# schematic-version2.net
KiCad netlist of a schematic drawn in EAGLE
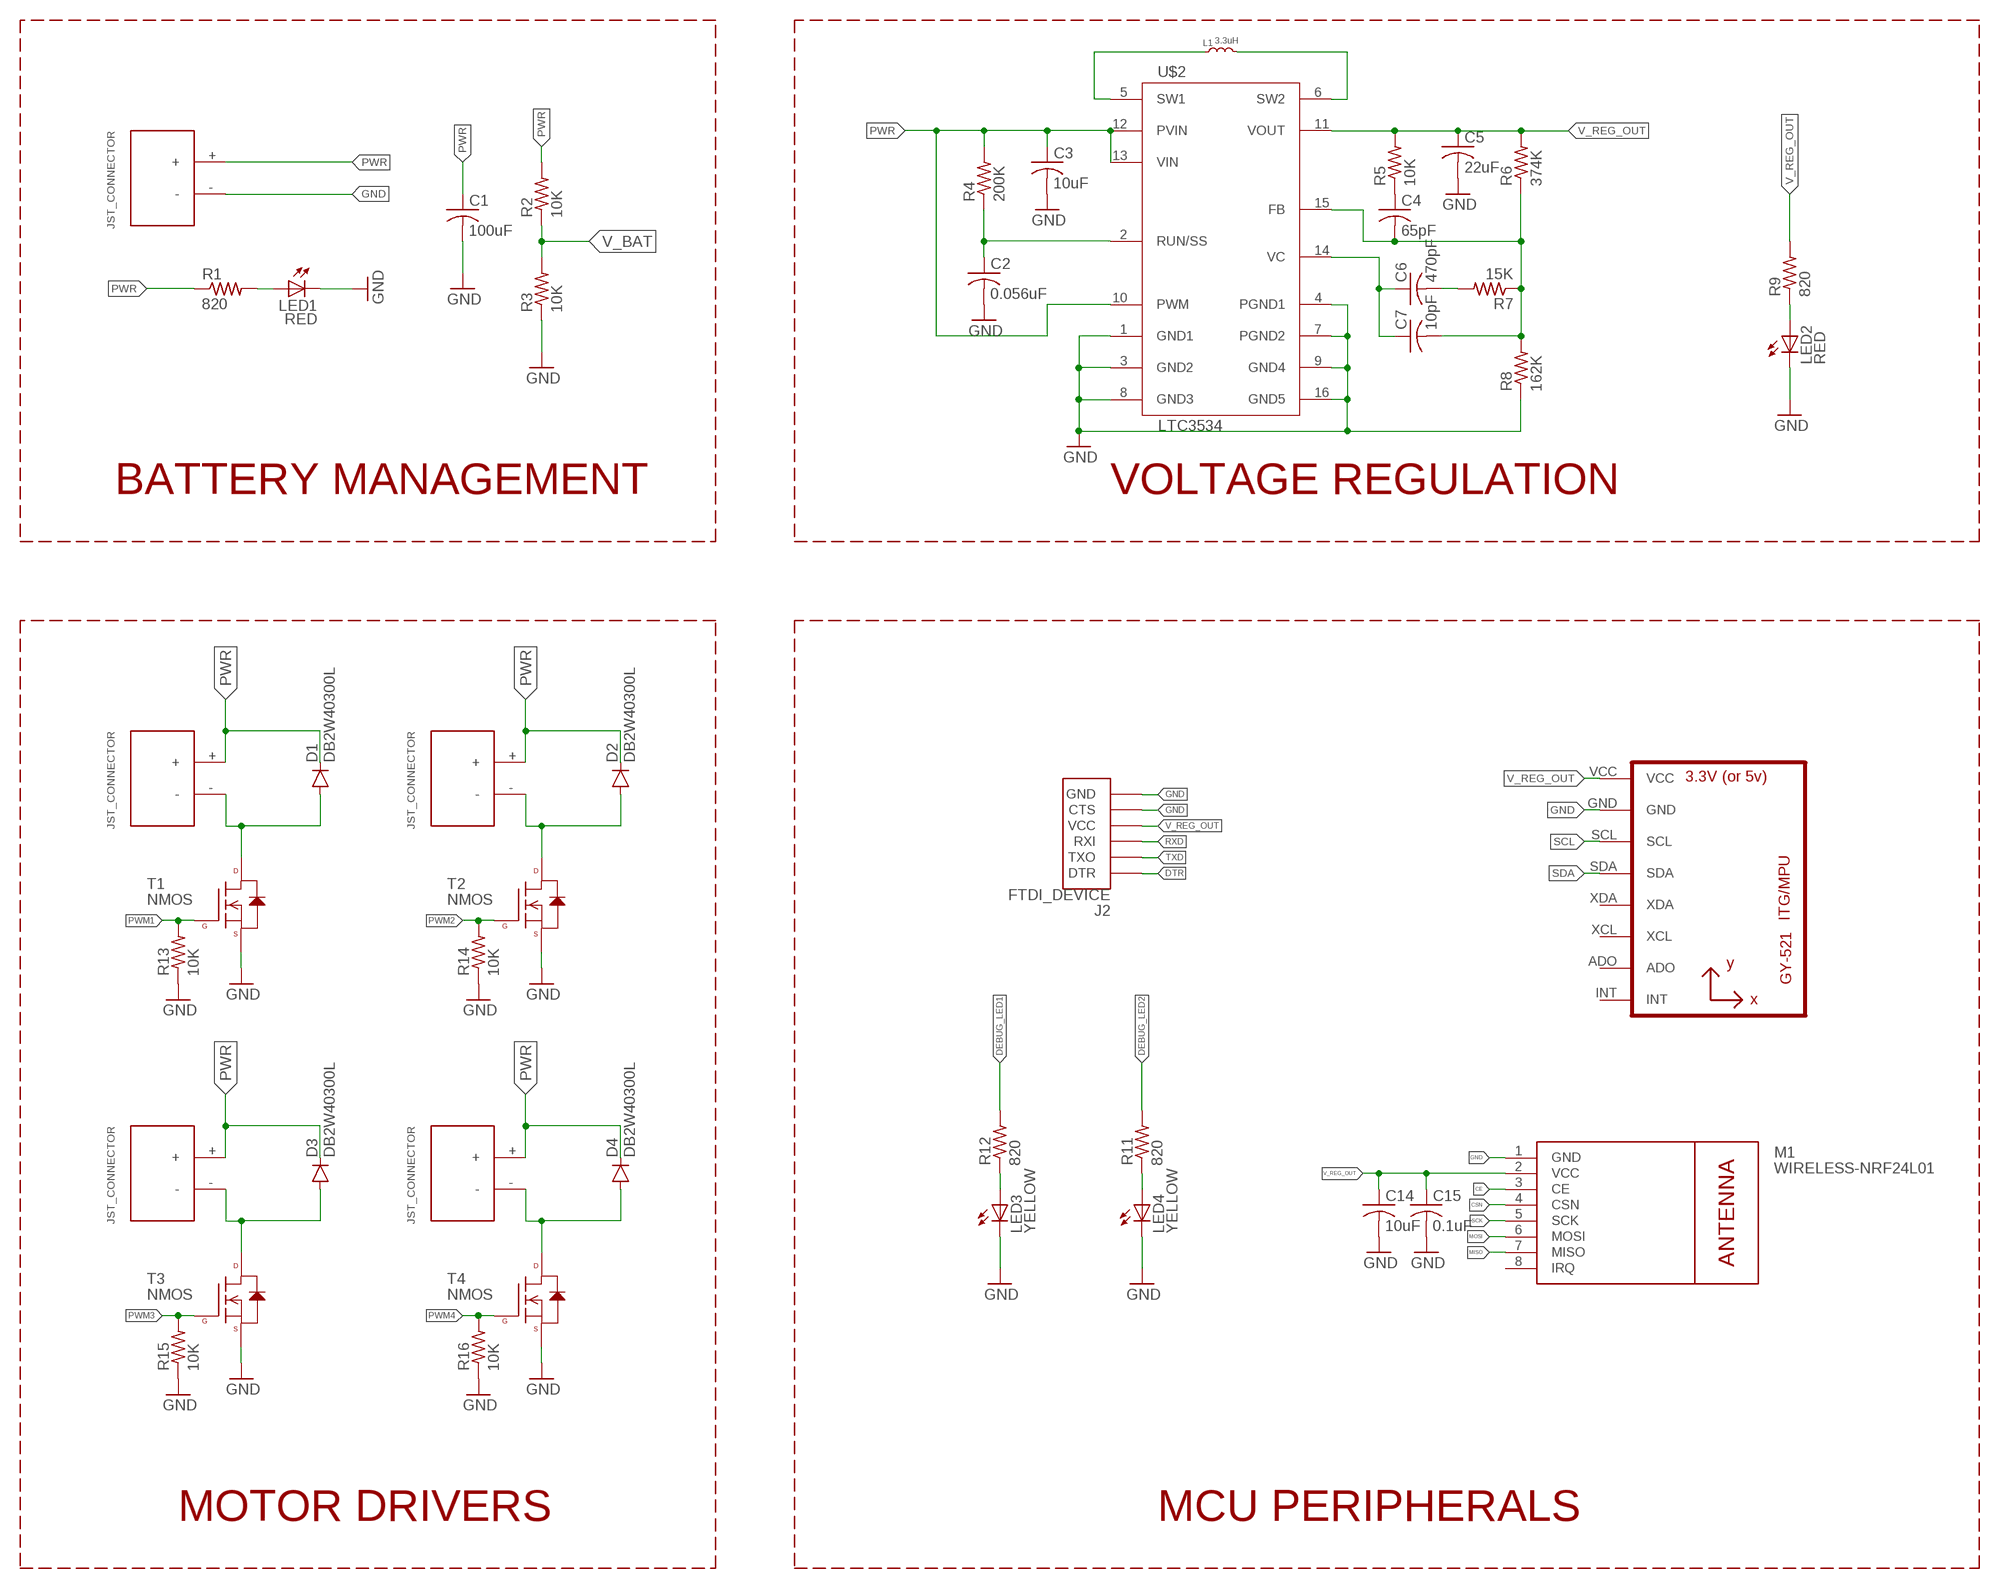
[diagram p0: schematic, sheet 1, part 1 of 2]
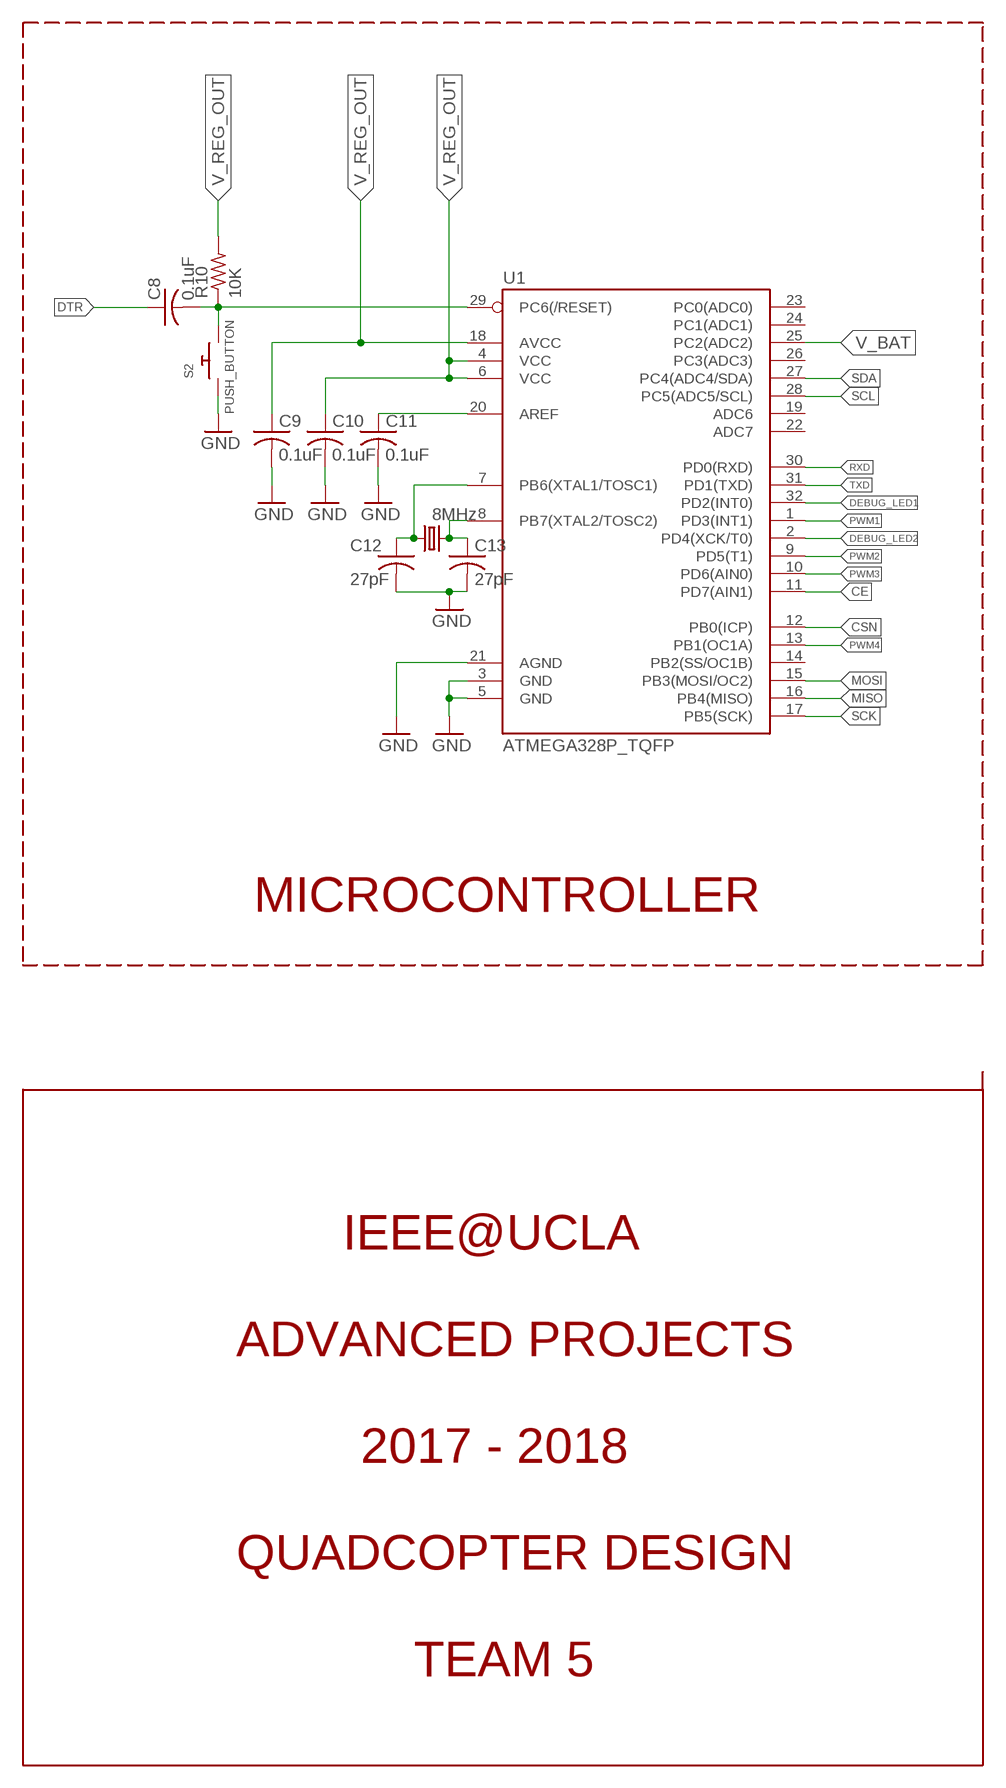
[diagram p1: schematic, sheet 1, part 2 of 2]

(export (version "E")
  (design (tool "Eeschema 10.0.6"))
  (components
    (comp (ref "C1")
      (value "100uF")
      (footprint "eagle-import:C1210")
      (libsource (lib "eagle-import") (part "C-USC1210"))
    )
    (comp (ref "C2")
      (value "0.056uF")
      (footprint "eagle-import:C0603")
      (libsource (lib "eagle-import") (part "resistor_348_C-USC0603"))
    )
    (comp (ref "C3")
      (value "10uF")
      (footprint "eagle-import:C0603")
      (libsource (lib "eagle-import") (part "resistor_348_C-USC0603"))
    )
    (comp (ref "C4")
      (value "65pF")
      (footprint "eagle-import:C1206")
      (libsource (lib "eagle-import") (part "C-USC1206"))
    )
    (comp (ref "C5")
      (value "22uF")
      (footprint "eagle-import:C0603")
      (libsource (lib "eagle-import") (part "resistor_348_C-USC0603"))
    )
    (comp (ref "C6")
      (value "470pF")
      (footprint "eagle-import:C0603")
      (libsource (lib "eagle-import") (part "resistor_348_C-USC0603"))
    )
    (comp (ref "C7")
      (value "10pF")
      (footprint "eagle-import:C0603")
      (libsource (lib "eagle-import") (part "resistor_348_C-USC0603"))
    )
    (comp (ref "C8")
      (value "0.1uF")
      (footprint "eagle-import:C0603")
      (libsource (lib "eagle-import") (part "C-USC0603"))
    )
    (comp (ref "C9")
      (value "0.1uF")
      (footprint "eagle-import:C0603")
      (libsource (lib "eagle-import") (part "C-USC0603"))
    )
    (comp (ref "C10")
      (value "0.1uF")
      (footprint "eagle-import:C0603")
      (libsource (lib "eagle-import") (part "C-USC0603"))
    )
    (comp (ref "C11")
      (value "0.1uF")
      (footprint "eagle-import:C0603")
      (libsource (lib "eagle-import") (part "C-USC0603"))
    )
    (comp (ref "C12")
      (value "27pF")
      (footprint "eagle-import:C0603")
      (libsource (lib "eagle-import") (part "resistor_348_C-USC0603"))
    )
    (comp (ref "C13")
      (value "27pF")
      (footprint "eagle-import:C0603")
      (libsource (lib "eagle-import") (part "resistor_348_C-USC0603"))
    )
    (comp (ref "C14")
      (value "10uF")
      (footprint "eagle-import:C0603")
      (libsource (lib "eagle-import") (part "resistor_348_C-USC0603"))
    )
    (comp (ref "C15")
      (value "0.1uF")
      (footprint "eagle-import:C0603")
      (libsource (lib "eagle-import") (part "resistor_348_C-USC0603"))
    )
    (comp (ref "D1")
      (value "DB2W40300L")
      (footprint "eagle-import:MINI2-F3-B")
      (libsource (lib "eagle-import") (part "DB2W40300L"))
    )
    (comp (ref "D2")
      (value "DB2W40300L")
      (footprint "eagle-import:MINI2-F3-B")
      (libsource (lib "eagle-import") (part "DB2W40300L"))
    )
    (comp (ref "D3")
      (value "DB2W40300L")
      (footprint "eagle-import:MINI2-F3-B")
      (libsource (lib "eagle-import") (part "DB2W40300L"))
    )
    (comp (ref "D4")
      (value "DB2W40300L")
      (footprint "eagle-import:MINI2-F3-B")
      (libsource (lib "eagle-import") (part "DB2W40300L"))
    )
    (comp (ref "J2")
      (value "FTDI_DEVICE")
      (footprint "eagle-import:FTDI_DEVICE_SIDE")
      (libsource (lib "eagle-import") (part "FTDI_DEVICE"))
    )
    (comp (ref "L1")
      (value "3.3uH")
      (footprint "eagle-import:XAL4020")
      (libsource (lib "eagle-import") (part "INDUCTOR.XAL4020"))
    )
    (comp (ref "LED1")
      (value "RED")
      (footprint "eagle-import:SML0603")
      (libsource (lib "eagle-import") (part "LEDSML0603"))
    )
    (comp (ref "LED2")
      (value "RED")
      (footprint "eagle-import:SML0603")
      (libsource (lib "eagle-import") (part "LEDSML0603"))
    )
    (comp (ref "LED3")
      (value "YELLOW")
      (footprint "eagle-import:SML0603")
      (libsource (lib "eagle-import") (part "LEDSML0603"))
    )
    (comp (ref "LED4")
      (value "YELLOW")
      (footprint "eagle-import:SML0603")
      (libsource (lib "eagle-import") (part "LEDSML0603"))
    )
    (comp (ref "M1")
      (value "WIRELESS-NRF24L01")
      (footprint "eagle-import:WIRELESS-NRF24L01")
      (libsource (lib "eagle-import") (part "WIRELESS-NRF24L01"))
    )
    (comp (ref "Q1")
      (value "8MHz")
      (footprint "eagle-import:CSM-7X-DU")
      (libsource (lib "eagle-import") (part "CSM-7X-DU"))
    )
    (comp (ref "R1")
      (value "820")
      (footprint "eagle-import:R0603")
      (libsource (lib "eagle-import") (part "R-US_R0603"))
    )
    (comp (ref "R2")
      (value "10K")
      (footprint "eagle-import:R0603")
      (libsource (lib "eagle-import") (part "resistor_348_R-US_R0603"))
    )
    (comp (ref "R3")
      (value "10K")
      (footprint "eagle-import:R0603")
      (libsource (lib "eagle-import") (part "resistor_348_R-US_R0603"))
    )
    (comp (ref "R4")
      (value "200K")
      (footprint "eagle-import:R0603")
      (libsource (lib "eagle-import") (part "resistor_348_R-US_R0603"))
    )
    (comp (ref "R5")
      (value "10K")
      (footprint "eagle-import:R0603")
      (libsource (lib "eagle-import") (part "resistor_348_R-US_R0603"))
    )
    (comp (ref "R6")
      (value "374K")
      (footprint "eagle-import:R0603")
      (libsource (lib "eagle-import") (part "resistor_348_R-US_R0603"))
    )
    (comp (ref "R7")
      (value "15K")
      (footprint "eagle-import:R0603")
      (libsource (lib "eagle-import") (part "resistor_348_R-US_R0603"))
    )
    (comp (ref "R8")
      (value "162K")
      (footprint "eagle-import:R0603")
      (libsource (lib "eagle-import") (part "resistor_348_R-US_R0603"))
    )
    (comp (ref "R9")
      (value "820")
      (footprint "eagle-import:R0603")
      (libsource (lib "eagle-import") (part "R-US_R0603"))
    )
    (comp (ref "R10")
      (value "10K")
      (footprint "eagle-import:R0603")
      (libsource (lib "eagle-import") (part "resistor_348_R-US_R0603"))
    )
    (comp (ref "R11")
      (value "820")
      (footprint "eagle-import:R0603")
      (libsource (lib "eagle-import") (part "R-US_R0603"))
    )
    (comp (ref "R12")
      (value "820")
      (footprint "eagle-import:R0603")
      (libsource (lib "eagle-import") (part "R-US_R0603"))
    )
    (comp (ref "R13")
      (value "10K")
      (footprint "eagle-import:R0603")
      (libsource (lib "eagle-import") (part "resistor_348_R-US_R0603"))
    )
    (comp (ref "R14")
      (value "10K")
      (footprint "eagle-import:R0603")
      (libsource (lib "eagle-import") (part "resistor_348_R-US_R0603"))
    )
    (comp (ref "R15")
      (value "10K")
      (footprint "eagle-import:R0603")
      (libsource (lib "eagle-import") (part "resistor_348_R-US_R0603"))
    )
    (comp (ref "R16")
      (value "10K")
      (footprint "eagle-import:R0603")
      (libsource (lib "eagle-import") (part "resistor_348_R-US_R0603"))
    )
    (comp (ref "S2")
      (value "PUSH_BUTTON")
      (footprint "eagle-import:PUSHBUTTON_SMD_SJ")
      (libsource (lib "eagle-import") (part "SWITCH_PUSHBUTTONSOFTTOUCHSMD_SJ"))
    )
    (comp (ref "T1")
      (value "NMOS")
      (footprint "eagle-import:SOT23-3")
      (libsource (lib "eagle-import") (part "N-CHANNEL-MOSFET-IRLML6244TRPBF"))
    )
    (comp (ref "T2")
      (value "NMOS")
      (footprint "eagle-import:SOT23-3")
      (libsource (lib "eagle-import") (part "N-CHANNEL-MOSFET-IRLML6244TRPBF"))
    )
    (comp (ref "T3")
      (value "NMOS")
      (footprint "eagle-import:SOT23-3")
      (libsource (lib "eagle-import") (part "N-CHANNEL-MOSFET-IRLML6244TRPBF"))
    )
    (comp (ref "T4")
      (value "NMOS")
      (footprint "eagle-import:SOT23-3")
      (libsource (lib "eagle-import") (part "N-CHANNEL-MOSFET-IRLML6244TRPBF"))
    )
    (comp (ref "U$1")
      (value "JST_CONNECTOR_FEMALE")
      (footprint "eagle-import:JST_CONNECTOR_FEMALE")
      (libsource (lib "eagle-import") (part "JST_CONNECTOR_FEMALE"))
    )
    (comp (ref "U$2")
      (value "LTC3534")
      (footprint "eagle-import:SSOP-16GN")
      (libsource (lib "eagle-import") (part "LTC3534"))
    )
    (comp (ref "U$4")
      (value "JST_CONNECTOR_FEMALE")
      (footprint "eagle-import:JST_CONNECTOR_FEMALE")
      (libsource (lib "eagle-import") (part "JST_CONNECTOR_FEMALE"))
    )
    (comp (ref "U$7")
      (value "JST_CONNECTOR_FEMALE")
      (footprint "eagle-import:JST_CONNECTOR_FEMALE")
      (libsource (lib "eagle-import") (part "JST_CONNECTOR_FEMALE"))
    )
    (comp (ref "U$10")
      (value "JST_CONNECTOR_FEMALE")
      (footprint "eagle-import:JST_CONNECTOR_FEMALE")
      (libsource (lib "eagle-import") (part "JST_CONNECTOR_FEMALE"))
    )
    (comp (ref "U$13")
      (value "JST_CONNECTOR_FEMALE")
      (footprint "eagle-import:JST_CONNECTOR_FEMALE")
      (libsource (lib "eagle-import") (part "JST_CONNECTOR_FEMALE"))
    )
    (comp (ref "U1")
      (value "ATMEGA328P_TQFP")
      (footprint "eagle-import:TQFP32-08")
      (libsource (lib "eagle-import") (part "ATMEGA328P_TQFP"))
    )
    (comp (ref "U2")
      (value "GY-521MPU6050")
      (footprint "eagle-import:GY-521")
      (libsource (lib "eagle-import") (part "GY-521MPU6050"))
    )
  )
  (nets
    (net (code "1") (name "CE") (class "Default")
      (node (ref "M1") (pin "3") (pinfunction "CE_3") (pintype "bidirectional"))
      (node (ref "U1") (pin "11") (pinfunction "PD7(AIN1)_11") (pintype "bidirectional"))
    )
    (net (code "2") (name "CSN") (class "Default")
      (node (ref "M1") (pin "4") (pinfunction "CSN_4") (pintype "bidirectional"))
      (node (ref "U1") (pin "12") (pinfunction "PB0(ICP)_12") (pintype "bidirectional"))
    )
    (net (code "3") (name "DEBUG_LED1") (class "Default")
      (node (ref "R12") (pin "2") (pinfunction "2_2") (pintype "passive"))
      (node (ref "U1") (pin "32") (pinfunction "PD2(INT0)_32") (pintype "bidirectional"))
    )
    (net (code "4") (name "DEBUG_LED2") (class "Default")
      (node (ref "R11") (pin "2") (pinfunction "2_2") (pintype "passive"))
      (node (ref "U1") (pin "2") (pinfunction "PD4(XCK/T0)_2") (pintype "bidirectional"))
    )
    (net (code "5") (name "DTR") (class "Default")
      (node (ref "C8") (pin "1") (pinfunction "1_1") (pintype "passive"))
      (node (ref "J2") (pin "P$1") (pinfunction "DTR_P$1") (pintype "bidirectional"))
    )
    (net (code "6") (name "GND") (class "Default")
      (node (ref "C1") (pin "2") (pinfunction "2_2") (pintype "passive"))
      (node (ref "C10") (pin "2") (pinfunction "2_2") (pintype "passive"))
      (node (ref "C11") (pin "2") (pinfunction "2_2") (pintype "passive"))
      (node (ref "C12") (pin "2") (pinfunction "2_2") (pintype "passive"))
      (node (ref "C13") (pin "2") (pinfunction "2_2") (pintype "passive"))
      (node (ref "C14") (pin "2") (pinfunction "2_2") (pintype "passive"))
      (node (ref "C15") (pin "2") (pinfunction "2_2") (pintype "passive"))
      (node (ref "C2") (pin "2") (pinfunction "2_2") (pintype "passive"))
      (node (ref "C3") (pin "2") (pinfunction "2_2") (pintype "passive"))
      (node (ref "C5") (pin "2") (pinfunction "2_2") (pintype "passive"))
      (node (ref "C9") (pin "2") (pinfunction "2_2") (pintype "passive"))
      (node (ref "J2") (pin "P$5") (pinfunction "CTS_P$5") (pintype "bidirectional"))
      (node (ref "J2") (pin "P$6") (pinfunction "GND_P$6") (pintype "bidirectional"))
      (node (ref "LED1") (pin "C") (pinfunction "C_C") (pintype "passive"))
      (node (ref "LED2") (pin "C") (pinfunction "C_C") (pintype "passive"))
      (node (ref "LED3") (pin "C") (pinfunction "C_C") (pintype "passive"))
      (node (ref "LED4") (pin "C") (pinfunction "C_C") (pintype "passive"))
      (node (ref "M1") (pin "1") (pinfunction "GND_1") (pintype "power_in"))
      (node (ref "R13") (pin "1") (pinfunction "1_1") (pintype "passive"))
      (node (ref "R14") (pin "1") (pinfunction "1_1") (pintype "passive"))
      (node (ref "R15") (pin "1") (pinfunction "1_1") (pintype "passive"))
      (node (ref "R16") (pin "1") (pinfunction "1_1") (pintype "passive"))
      (node (ref "R3") (pin "1") (pinfunction "1_1") (pintype "passive"))
      (node (ref "R8") (pin "1") (pinfunction "1_1") (pintype "passive"))
      (node (ref "S2") (pin "P$1") (pinfunction "P$1_P$1") (pintype "passive"))
      (node (ref "T1") (pin "2") (pinfunction "S_2") (pintype "passive"))
      (node (ref "T2") (pin "2") (pinfunction "S_2") (pintype "passive"))
      (node (ref "T3") (pin "2") (pinfunction "S_2") (pintype "passive"))
      (node (ref "T4") (pin "2") (pinfunction "S_2") (pintype "passive"))
      (node (ref "U$1") (pin "-") (pinfunction "-_-") (pintype "bidirectional"))
      (node (ref "U$2") (pin "1") (pinfunction "GND1_1") (pintype "bidirectional"))
      (node (ref "U$2") (pin "16") (pinfunction "GND5_16") (pintype "bidirectional"))
      (node (ref "U$2") (pin "3") (pinfunction "GND2_3") (pintype "bidirectional"))
      (node (ref "U$2") (pin "4") (pinfunction "PGND1_4") (pintype "bidirectional"))
      (node (ref "U$2") (pin "7") (pinfunction "PGND2_7") (pintype "bidirectional"))
      (node (ref "U$2") (pin "8") (pinfunction "GND3_8") (pintype "bidirectional"))
      (node (ref "U$2") (pin "9") (pinfunction "GND4_9") (pintype "bidirectional"))
      (node (ref "U1") (pin "21") (pinfunction "AGND_21") (pintype "bidirectional"))
      (node (ref "U1") (pin "3") (pinfunction "GND_3") (pintype "bidirectional"))
      (node (ref "U1") (pin "5") (pinfunction "GND_5") (pintype "bidirectional"))
      (node (ref "U2") (pin "GND") (pinfunction "GND_GND") (pintype "bidirectional"))
    )
    (net (code "7") (name "MISO") (class "Default")
      (node (ref "M1") (pin "7") (pinfunction "MISO_7") (pintype "bidirectional"))
      (node (ref "U1") (pin "16") (pinfunction "PB4(MISO)_16") (pintype "bidirectional"))
    )
    (net (code "8") (name "MOSI") (class "Default")
      (node (ref "M1") (pin "6") (pinfunction "MOSI_6") (pintype "bidirectional"))
      (node (ref "U1") (pin "15") (pinfunction "PB3(MOSI/OC2)_15") (pintype "bidirectional"))
    )
    (net (code "9") (name "Net-(C4-Pad1)") (class "Default")
      (node (ref "C4") (pin "1") (pinfunction "1_1") (pintype "passive"))
      (node (ref "R5") (pin "1") (pinfunction "1_1") (pintype "passive"))
    )
    (net (code "10") (name "Net-(C6-Pad2)") (class "Default")
      (node (ref "C6") (pin "2") (pinfunction "2_2") (pintype "passive"))
      (node (ref "R7") (pin "2") (pinfunction "2_2") (pintype "passive"))
    )
    (net (code "11") (name "Net-(D1-PPIN)") (class "Default")
      (node (ref "D1") (pin "POS") (pinfunction "PPIN_POS") (pintype "passive"))
      (node (ref "T1") (pin "3") (pinfunction "D_3") (pintype "passive"))
      (node (ref "U$4") (pin "-") (pinfunction "-_-") (pintype "bidirectional"))
    )
    (net (code "12") (name "Net-(D2-PPIN)") (class "Default")
      (node (ref "D2") (pin "POS") (pinfunction "PPIN_POS") (pintype "passive"))
      (node (ref "T2") (pin "3") (pinfunction "D_3") (pintype "passive"))
      (node (ref "U$7") (pin "-") (pinfunction "-_-") (pintype "bidirectional"))
    )
    (net (code "13") (name "Net-(D3-PPIN)") (class "Default")
      (node (ref "D3") (pin "POS") (pinfunction "PPIN_POS") (pintype "passive"))
      (node (ref "T3") (pin "3") (pinfunction "D_3") (pintype "passive"))
      (node (ref "U$10") (pin "-") (pinfunction "-_-") (pintype "bidirectional"))
    )
    (net (code "14") (name "Net-(D4-PPIN)") (class "Default")
      (node (ref "D4") (pin "POS") (pinfunction "PPIN_POS") (pintype "passive"))
      (node (ref "T4") (pin "3") (pinfunction "D_3") (pintype "passive"))
      (node (ref "U$13") (pin "-") (pinfunction "-_-") (pintype "bidirectional"))
    )
    (net (code "15") (name "Net-(LED1-PadA)") (class "Default")
      (node (ref "LED1") (pin "A") (pinfunction "A_A") (pintype "passive"))
      (node (ref "R1") (pin "2") (pinfunction "2_2") (pintype "passive"))
    )
    (net (code "16") (name "Net-(LED2-PadA)") (class "Default")
      (node (ref "LED2") (pin "A") (pinfunction "A_A") (pintype "passive"))
      (node (ref "R9") (pin "1") (pinfunction "1_1") (pintype "passive"))
    )
    (net (code "17") (name "Net-(LED3-PadA)") (class "Default")
      (node (ref "LED3") (pin "A") (pinfunction "A_A") (pintype "passive"))
      (node (ref "R12") (pin "1") (pinfunction "1_1") (pintype "passive"))
    )
    (net (code "18") (name "Net-(LED4-PadA)") (class "Default")
      (node (ref "LED4") (pin "A") (pinfunction "A_A") (pintype "passive"))
      (node (ref "R11") (pin "1") (pinfunction "1_1") (pintype "passive"))
    )
    (net (code "19") (name "Net-(U$2-FB)") (class "Default")
      (node (ref "C4") (pin "2") (pinfunction "2_2") (pintype "passive"))
      (node (ref "C7") (pin "2") (pinfunction "2_2") (pintype "passive"))
      (node (ref "R6") (pin "1") (pinfunction "1_1") (pintype "passive"))
      (node (ref "R7") (pin "1") (pinfunction "1_1") (pintype "passive"))
      (node (ref "R8") (pin "2") (pinfunction "2_2") (pintype "passive"))
      (node (ref "U$2") (pin "15") (pinfunction "FB_15") (pintype "bidirectional"))
    )
    (net (code "20") (name "Net-(U$2-RUN{slash}SS)") (class "Default")
      (node (ref "C2") (pin "1") (pinfunction "1_1") (pintype "passive"))
      (node (ref "R4") (pin "1") (pinfunction "1_1") (pintype "passive"))
      (node (ref "U$2") (pin "2") (pinfunction "RUN/SS_2") (pintype "bidirectional"))
    )
    (net (code "21") (name "Net-(U$2-SW1)") (class "Default")
      (node (ref "L1") (pin "1") (pinfunction "1_1") (pintype "passive"))
      (node (ref "U$2") (pin "5") (pinfunction "SW1_5") (pintype "bidirectional"))
    )
    (net (code "22") (name "Net-(U$2-SW2)") (class "Default")
      (node (ref "L1") (pin "2") (pinfunction "2_2") (pintype "passive"))
      (node (ref "U$2") (pin "6") (pinfunction "SW2_6") (pintype "bidirectional"))
    )
    (net (code "23") (name "Net-(U$2-VC)") (class "Default")
      (node (ref "C6") (pin "1") (pinfunction "1_1") (pintype "passive"))
      (node (ref "C7") (pin "1") (pinfunction "1_1") (pintype "passive"))
      (node (ref "U$2") (pin "14") (pinfunction "VC_14") (pintype "bidirectional"))
    )
    (net (code "24") (name "Net-(U1-AREF)") (class "Default")
      (node (ref "C11") (pin "1") (pinfunction "1_1") (pintype "passive"))
      (node (ref "U1") (pin "20") (pinfunction "AREF_20") (pintype "bidirectional"))
    )
    (net (code "25") (name "Net-(U1-PB6(XTAL1{slash}TOSC1))") (class "Default")
      (node (ref "C12") (pin "1") (pinfunction "1_1") (pintype "passive"))
      (node (ref "Q1") (pin "1") (pinfunction "1_1") (pintype "passive"))
      (node (ref "U1") (pin "7") (pinfunction "PB6(XTAL1/TOSC1)_7") (pintype "bidirectional"))
    )
    (net (code "26") (name "Net-(U1-PB7(XTAL2{slash}TOSC2))") (class "Default")
      (node (ref "C13") (pin "1") (pinfunction "1_1") (pintype "passive"))
      (node (ref "Q1") (pin "2") (pinfunction "2_2") (pintype "passive"))
      (node (ref "U1") (pin "8") (pinfunction "PB7(XTAL2/TOSC2)_8") (pintype "bidirectional"))
    )
    (net (code "27") (name "Net-(U1-PC6({slash}RESET))") (class "Default")
      (node (ref "C8") (pin "2") (pinfunction "2_2") (pintype "passive"))
      (node (ref "R10") (pin "1") (pinfunction "1_1") (pintype "passive"))
      (node (ref "S2") (pin "P$2") (pinfunction "P$2_P$2") (pintype "passive"))
      (node (ref "U1") (pin "29") (pinfunction "PC6(/RESET)_29") (pintype "bidirectional"))
    )
    (net (code "28") (name "PWM1") (class "Default")
      (node (ref "R13") (pin "2") (pinfunction "2_2") (pintype "passive"))
      (node (ref "T1") (pin "1") (pinfunction "G_1") (pintype "passive"))
      (node (ref "U1") (pin "1") (pinfunction "PD3(INT1)_1") (pintype "bidirectional"))
    )
    (net (code "29") (name "PWM2") (class "Default")
      (node (ref "R14") (pin "2") (pinfunction "2_2") (pintype "passive"))
      (node (ref "T2") (pin "1") (pinfunction "G_1") (pintype "passive"))
      (node (ref "U1") (pin "9") (pinfunction "PD5(T1)_9") (pintype "bidirectional"))
    )
    (net (code "30") (name "PWM3") (class "Default")
      (node (ref "R15") (pin "2") (pinfunction "2_2") (pintype "passive"))
      (node (ref "T3") (pin "1") (pinfunction "G_1") (pintype "passive"))
      (node (ref "U1") (pin "10") (pinfunction "PD6(AIN0)_10") (pintype "bidirectional"))
    )
    (net (code "31") (name "PWM4") (class "Default")
      (node (ref "R16") (pin "2") (pinfunction "2_2") (pintype "passive"))
      (node (ref "T4") (pin "1") (pinfunction "G_1") (pintype "passive"))
      (node (ref "U1") (pin "13") (pinfunction "PB1(OC1A)_13") (pintype "bidirectional"))
    )
    (net (code "32") (name "PWR") (class "Default")
      (node (ref "C1") (pin "1") (pinfunction "1_1") (pintype "passive"))
      (node (ref "C3") (pin "1") (pinfunction "1_1") (pintype "passive"))
      (node (ref "D1") (pin "NEG") (pinfunction "GPIN_NEG") (pintype "passive"))
      (node (ref "D2") (pin "NEG") (pinfunction "GPIN_NEG") (pintype "passive"))
      (node (ref "D3") (pin "NEG") (pinfunction "GPIN_NEG") (pintype "passive"))
      (node (ref "D4") (pin "NEG") (pinfunction "GPIN_NEG") (pintype "passive"))
      (node (ref "R1") (pin "1") (pinfunction "1_1") (pintype "passive"))
      (node (ref "R2") (pin "2") (pinfunction "2_2") (pintype "passive"))
      (node (ref "R4") (pin "2") (pinfunction "2_2") (pintype "passive"))
      (node (ref "U$1") (pin "+") (pinfunction "+_+") (pintype "bidirectional"))
      (node (ref "U$10") (pin "+") (pinfunction "+_+") (pintype "bidirectional"))
      (node (ref "U$13") (pin "+") (pinfunction "+_+") (pintype "bidirectional"))
      (node (ref "U$2") (pin "10") (pinfunction "PWM_10") (pintype "bidirectional"))
      (node (ref "U$2") (pin "12") (pinfunction "PVIN_12") (pintype "bidirectional"))
      (node (ref "U$2") (pin "13") (pinfunction "VIN_13") (pintype "bidirectional"))
      (node (ref "U$4") (pin "+") (pinfunction "+_+") (pintype "bidirectional"))
      (node (ref "U$7") (pin "+") (pinfunction "+_+") (pintype "bidirectional"))
    )
    (net (code "33") (name "RXD") (class "Default")
      (node (ref "J2") (pin "P$3") (pinfunction "RXI_P$3") (pintype "bidirectional"))
      (node (ref "U1") (pin "30") (pinfunction "PD0(RXD)_30") (pintype "bidirectional"))
    )
    (net (code "34") (name "SCK") (class "Default")
      (node (ref "M1") (pin "5") (pinfunction "SCK_5") (pintype "bidirectional"))
      (node (ref "U1") (pin "17") (pinfunction "PB5(SCK)_17") (pintype "bidirectional"))
    )
    (net (code "35") (name "SCL") (class "Default")
      (node (ref "U1") (pin "28") (pinfunction "PC5(ADC5/SCL)_28") (pintype "bidirectional"))
      (node (ref "U2") (pin "SCL") (pinfunction "SCL_SCL") (pintype "bidirectional"))
    )
    (net (code "36") (name "SDA") (class "Default")
      (node (ref "U1") (pin "27") (pinfunction "PC4(ADC4/SDA)_27") (pintype "bidirectional"))
      (node (ref "U2") (pin "SDA") (pinfunction "SDA_SDA") (pintype "bidirectional"))
    )
    (net (code "37") (name "TXD") (class "Default")
      (node (ref "J2") (pin "P$2") (pinfunction "TXO_P$2") (pintype "bidirectional"))
      (node (ref "U1") (pin "31") (pinfunction "PD1(TXD)_31") (pintype "bidirectional"))
    )
    (net (code "38") (name "V_BAT") (class "Default")
      (node (ref "R2") (pin "1") (pinfunction "1_1") (pintype "passive"))
      (node (ref "R3") (pin "2") (pinfunction "2_2") (pintype "passive"))
      (node (ref "U1") (pin "25") (pinfunction "PC2(ADC2)_25") (pintype "bidirectional"))
    )
    (net (code "39") (name "V_REG_OUT") (class "Default")
      (node (ref "C10") (pin "1") (pinfunction "1_1") (pintype "passive"))
      (node (ref "C14") (pin "1") (pinfunction "1_1") (pintype "passive"))
      (node (ref "C15") (pin "1") (pinfunction "1_1") (pintype "passive"))
      (node (ref "C5") (pin "1") (pinfunction "1_1") (pintype "passive"))
      (node (ref "C9") (pin "1") (pinfunction "1_1") (pintype "passive"))
      (node (ref "J2") (pin "P$4") (pinfunction "VCC_P$4") (pintype "bidirectional"))
      (node (ref "M1") (pin "2") (pinfunction "VCC_2") (pintype "power_in"))
      (node (ref "R10") (pin "2") (pinfunction "2_2") (pintype "passive"))
      (node (ref "R5") (pin "2") (pinfunction "2_2") (pintype "passive"))
      (node (ref "R6") (pin "2") (pinfunction "2_2") (pintype "passive"))
      (node (ref "R9") (pin "2") (pinfunction "2_2") (pintype "passive"))
      (node (ref "U$2") (pin "11") (pinfunction "VOUT_11") (pintype "bidirectional"))
      (node (ref "U1") (pin "18") (pinfunction "AVCC_18") (pintype "bidirectional"))
      (node (ref "U1") (pin "4") (pinfunction "VCC_4") (pintype "bidirectional"))
      (node (ref "U1") (pin "6") (pinfunction "VCC_6") (pintype "bidirectional"))
      (node (ref "U2") (pin "VCC") (pinfunction "VCC_VCC") (pintype "bidirectional"))
    )
    (net (code "40") (name "unconnected-(M1-IRQ-Pad8)") (class "Default")
      (node (ref "M1") (pin "8") (pinfunction "IRQ_8") (pintype "bidirectional"))
    )
    (net (code "41") (name "unconnected-(U1-ADC6-Pad19)") (class "Default")
      (node (ref "U1") (pin "19") (pinfunction "ADC6_19") (pintype "bidirectional"))
    )
    (net (code "42") (name "unconnected-(U1-ADC7-Pad22)") (class "Default")
      (node (ref "U1") (pin "22") (pinfunction "ADC7_22") (pintype "bidirectional"))
    )
    (net (code "43") (name "unconnected-(U1-PB2(SS{slash}OC1B)-Pad14)") (class "Default")
      (node (ref "U1") (pin "14") (pinfunction "PB2(SS/OC1B)_14") (pintype "bidirectional"))
    )
    (net (code "44") (name "unconnected-(U1-PC0(ADC0)-Pad23)") (class "Default")
      (node (ref "U1") (pin "23") (pinfunction "PC0(ADC0)_23") (pintype "bidirectional"))
    )
    (net (code "45") (name "unconnected-(U1-PC1(ADC1)-Pad24)") (class "Default")
      (node (ref "U1") (pin "24") (pinfunction "PC1(ADC1)_24") (pintype "bidirectional"))
    )
    (net (code "46") (name "unconnected-(U1-PC3(ADC3)-Pad26)") (class "Default")
      (node (ref "U1") (pin "26") (pinfunction "PC3(ADC3)_26") (pintype "bidirectional"))
    )
    (net (code "47") (name "unconnected-(U2-PadADO)") (class "Default")
      (node (ref "U2") (pin "ADO") (pinfunction "ADO_ADO") (pintype "bidirectional"))
    )
    (net (code "48") (name "unconnected-(U2-PadINT)") (class "Default")
      (node (ref "U2") (pin "INT") (pinfunction "INT_INT") (pintype "bidirectional"))
    )
    (net (code "49") (name "unconnected-(U2-PadXCL)") (class "Default")
      (node (ref "U2") (pin "XCL") (pinfunction "XCL_XCL") (pintype "bidirectional"))
    )
    (net (code "50") (name "unconnected-(U2-PadXDA)") (class "Default")
      (node (ref "U2") (pin "XDA") (pinfunction "XDA_XDA") (pintype "bidirectional"))
    )
  )
)
